# current_limiter.net
KiCad netlist of a schematic drawn in Altium Designer
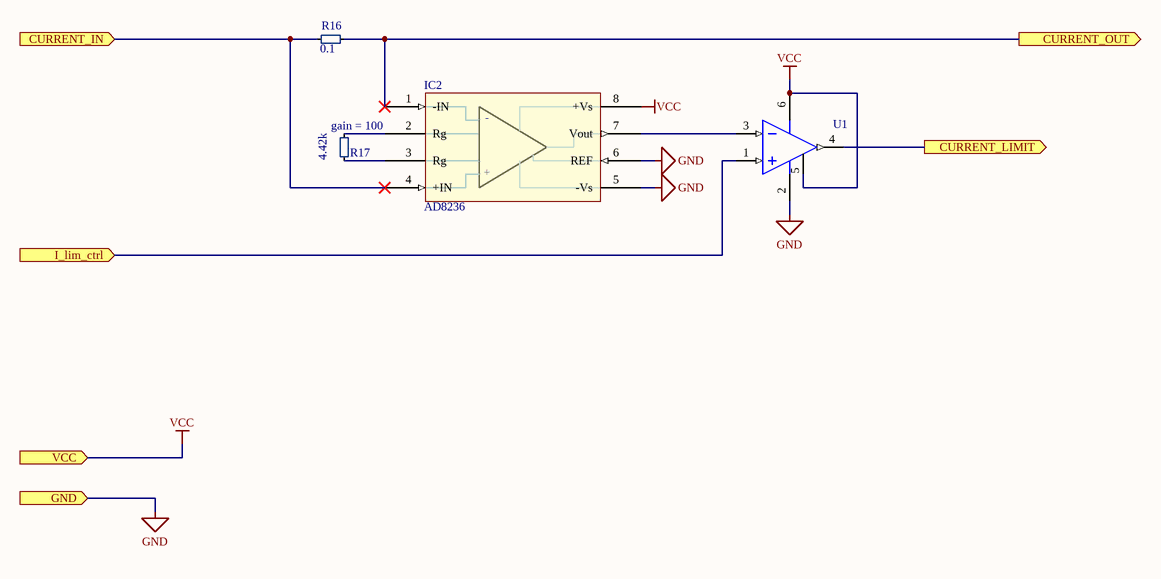
[diagram p0: current limiter.SchDoc]

(export (version "E")
  (design (tool "Eeschema 10.0.6"))
  (components
    (comp (ref "IC2")
      (value "AD8236")
      (footprint "8-MSOP")
      (description "IC OPAMP INSTR 23KHZ RRO 8MSOP")
      (libsource (lib "concord server") (part "AD8236"))
    )
    (comp (ref "R16")
      (value "ERJ-8BSFR10V")
      (footprint "Chip2PinSM127P600-8N")
      (fields (field (name "RESISTANCE") "0.1") (field (name "TOLERANCE") "1%"))
      (libsource (lib "concord server") (part "resistor_european"))
    )
    (comp (ref "R17")
      (value "RC0402FR-074K42L")
      (footprint "SMD_0402(1005)_M")
      (description "RES SMD 4.42K OHM 1% 1/16W 0402")
      (fields (field (name "RESISTANCE") "4.42k") (field (name "TOLERANCE") "1%"))
      (libsource (lib "concord server") (part "resistor_european"))
    )
    (comp (ref "U1")
      (value "LMV341IDBVR")
      (footprint "SOT95P280X145-6N")
      (description "Single Rail-To-Rail Output CMOS Operational Amplifier with Shutdown 6-SOT-23 -40 to 125")
      (libsource (lib "concord server") (part "LMV341IDBVR"))
    )
  )
  (nets
    (net (code "1") (name "/CURRENT_IN") (class "Default")
      (node (ref "IC2") (pin "4") (pinfunction "+IN_4") (pintype "input"))
      (node (ref "R16") (pin "1") (pinfunction "1_1") (pintype "passive"))
    )
    (net (code "2") (name "/CURRENT_LIMIT") (class "Default")
      (node (ref "U1") (pin "4") (pinfunction "OUT1_4") (pintype "output"))
    )
    (net (code "3") (name "/CURRENT_OUT") (class "Default")
      (node (ref "IC2") (pin "1") (pinfunction "-IN_1") (pintype "input"))
      (node (ref "R16") (pin "2") (pinfunction "2_2") (pintype "passive"))
    )
    (net (code "4") (name "/I_lim_ctrl") (class "Default")
      (node (ref "U1") (pin "1") (pinfunction "IN1+_1") (pintype "input"))
    )
    (net (code "5") (name "GND") (class "Default")
      (node (ref "IC2") (pin "5") (pinfunction "-Vs_5") (pintype "power_in"))
      (node (ref "IC2") (pin "6") (pinfunction "REF_6") (pintype "input"))
      (node (ref "U1") (pin "2") (pinfunction "VEE/GND_2") (pintype "power_in"))
    )
    (net (code "6") (name "Net-(IC2-Rg-Pad2)") (class "Default")
      (node (ref "IC2") (pin "2") (pinfunction "Rg_2") (pintype "passive"))
      (node (ref "R17") (pin "2") (pinfunction "2_2") (pintype "passive"))
    )
    (net (code "7") (name "Net-(IC2-Rg-Pad3)") (class "Default")
      (node (ref "IC2") (pin "3") (pinfunction "Rg_3") (pintype "passive"))
      (node (ref "R17") (pin "1") (pinfunction "1_1") (pintype "passive"))
    )
    (net (code "8") (name "Net-(IC2-Vout)") (class "Default")
      (node (ref "IC2") (pin "7") (pinfunction "Vout_7") (pintype "output"))
      (node (ref "U1") (pin "3") (pinfunction "IN1-_3") (pintype "input"))
    )
    (net (code "9") (name "VCC") (class "Default")
      (node (ref "IC2") (pin "8") (pinfunction "+Vs_8") (pintype "power_in"))
      (node (ref "U1") (pin "5") (pinfunction "!SHDN_5") (pintype "passive"))
      (node (ref "U1") (pin "6") (pinfunction "VCC_6") (pintype "power_in"))
    )
  )
)
